# G4-Coral.net
KiCad netlist of a schematic drawn in Altium Designer
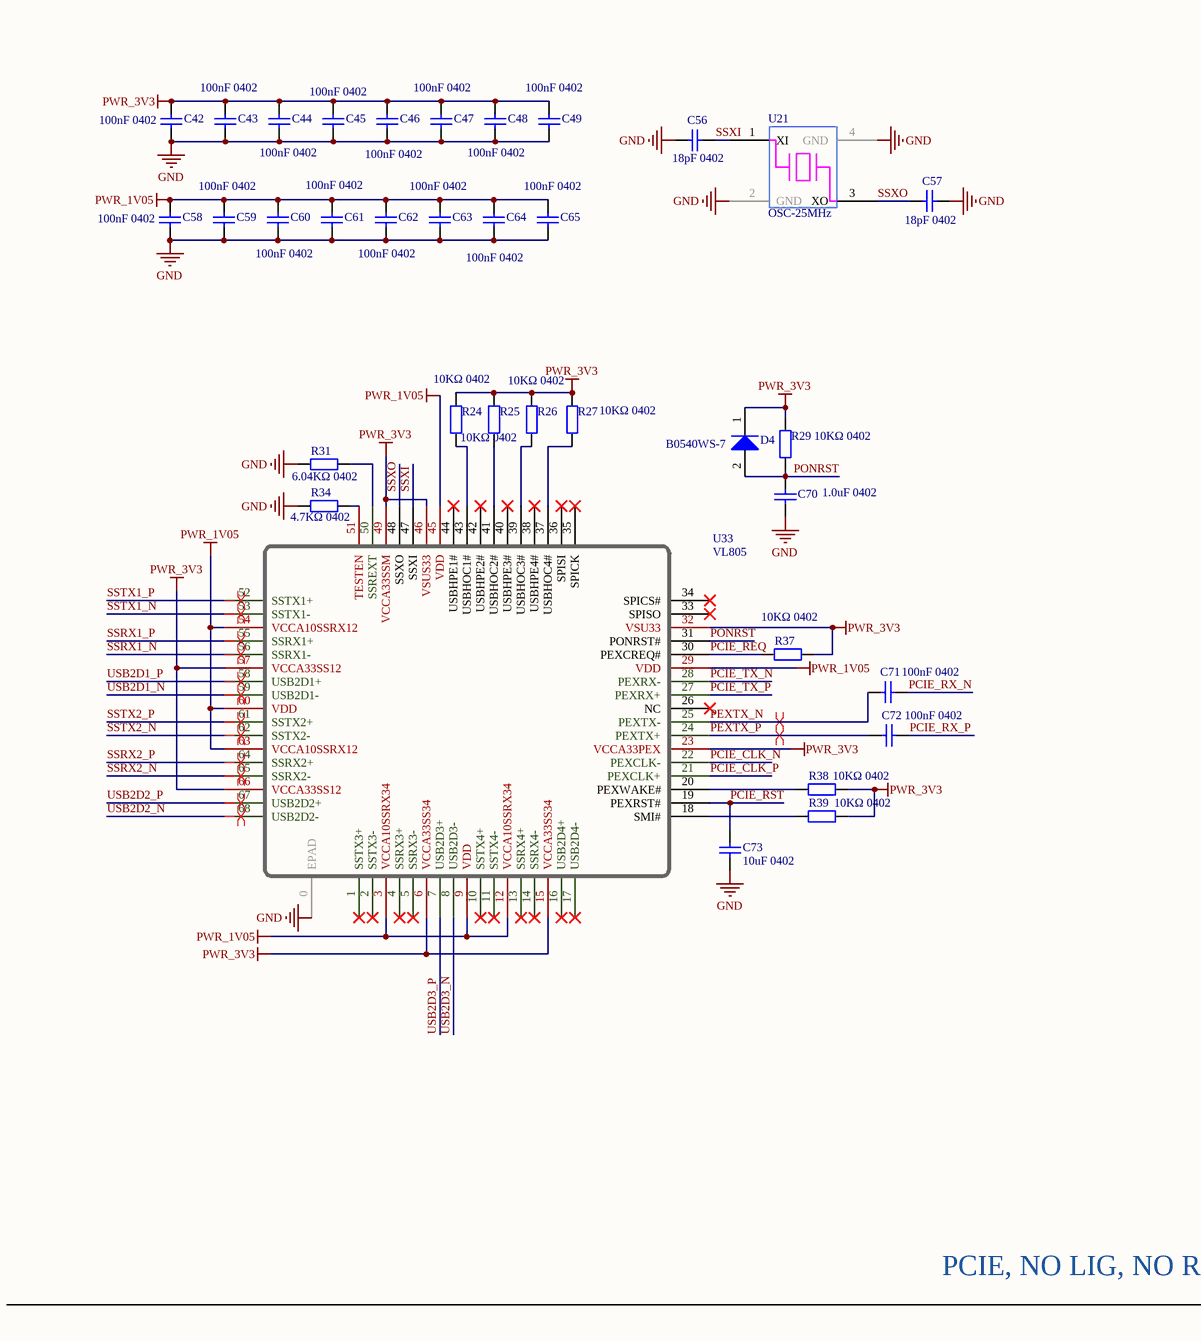
[diagram p0: G4-Coral.SchDoc, left]
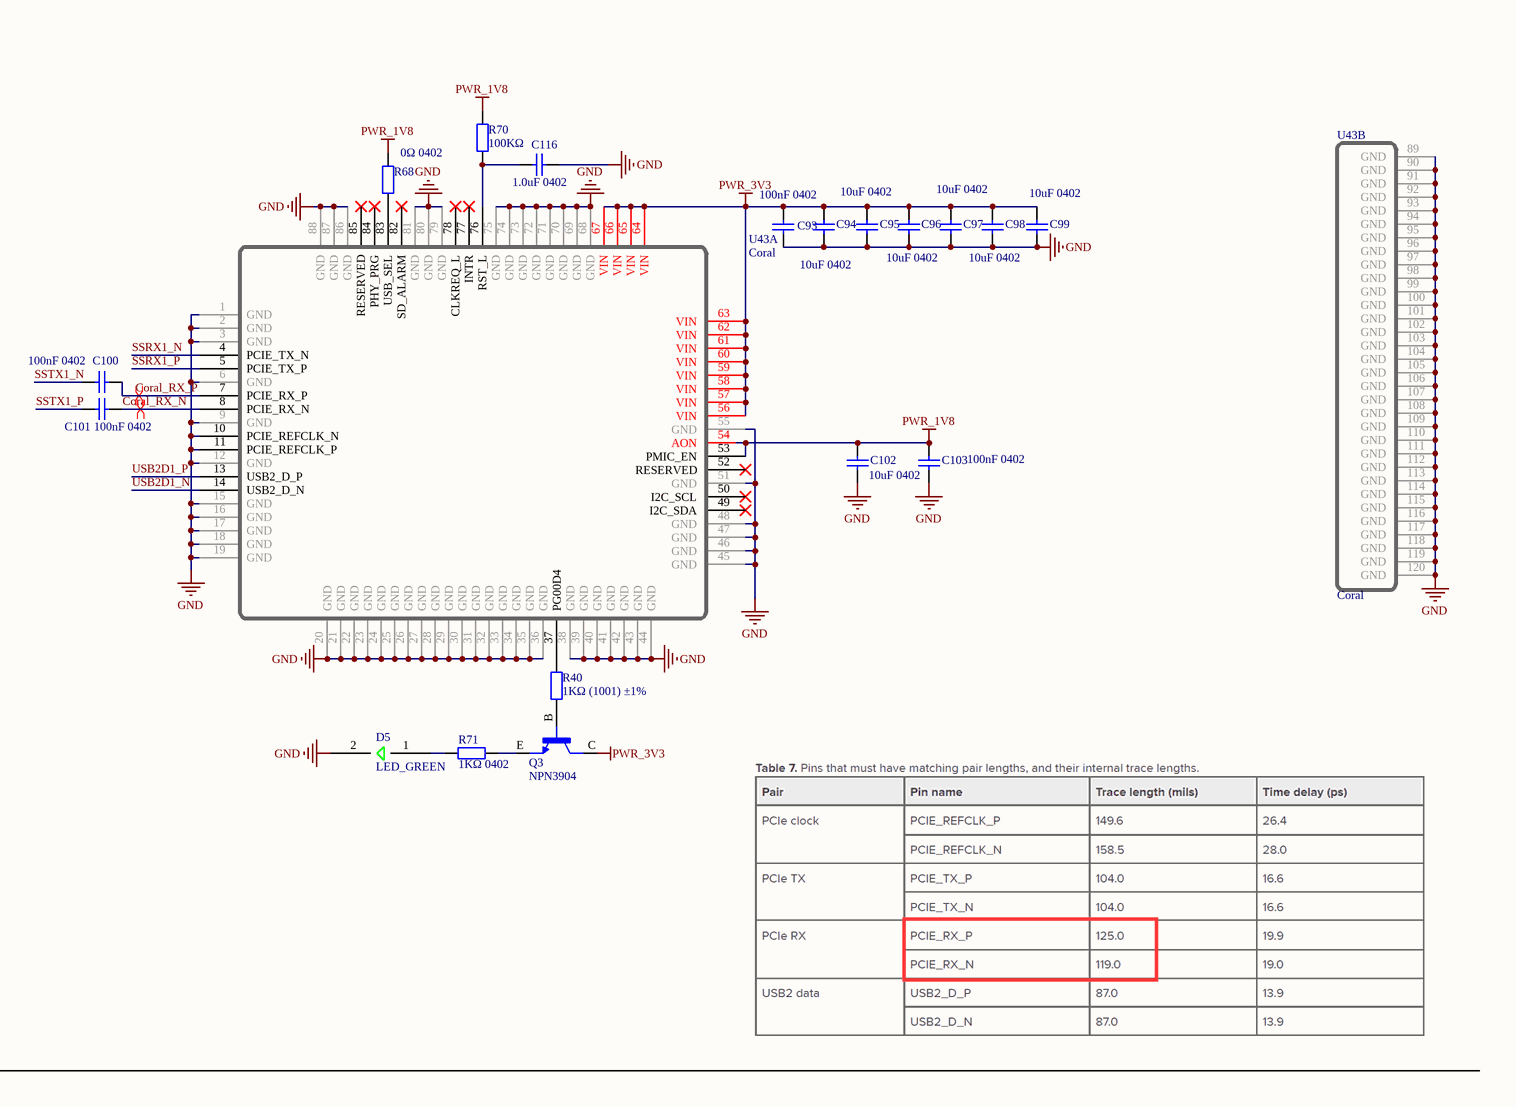
[diagram p1: G4-Coral.SchDoc, right]

(export (version "E")
  (design (tool "Eeschema 10.0.6"))
  (components
    (comp (ref "C42")
      (value "100nF 0402")
      (footprint "0402_C")
      (description "贴片电容")
      (libsource (lib "Miscellaneous Devices LC") (part "0402 100nF (104) 10% 16V"))
    )
    (comp (ref "C43")
      (value "100nF 0402")
      (footprint "0402_C")
      (description "贴片电容")
      (libsource (lib "Miscellaneous Devices LC") (part "0402 100nF (104) 10% 16V"))
    )
    (comp (ref "C44")
      (value "100nF 0402")
      (footprint "0402_C")
      (description "贴片电容")
      (libsource (lib "Miscellaneous Devices LC") (part "0402 100nF (104) 10% 16V"))
    )
    (comp (ref "C45")
      (value "100nF 0402")
      (footprint "0402_C")
      (description "贴片电容")
      (libsource (lib "Miscellaneous Devices LC") (part "0402 100nF (104) 10% 16V"))
    )
    (comp (ref "C46")
      (value "100nF 0402")
      (footprint "0402_C")
      (description "贴片电容")
      (libsource (lib "Miscellaneous Devices LC") (part "0402 100nF (104) 10% 16V"))
    )
    (comp (ref "C47")
      (value "100nF 0402")
      (footprint "0402_C")
      (description "贴片电容")
      (libsource (lib "Miscellaneous Devices LC") (part "0402 100nF (104) 10% 16V"))
    )
    (comp (ref "C48")
      (value "100nF 0402")
      (footprint "0402_C")
      (description "贴片电容")
      (libsource (lib "Miscellaneous Devices LC") (part "0402 100nF (104) 10% 16V"))
    )
    (comp (ref "C49")
      (value "100nF 0402")
      (footprint "0402_C")
      (description "贴片电容")
      (libsource (lib "Miscellaneous Devices LC") (part "0402 100nF (104) 10% 16V"))
    )
    (comp (ref "C56")
      (value "18pF 0402")
      (footprint "0402_C")
      (description "贴片电容")
      (libsource (lib "Miscellaneous Devices LC") (part "0402 18pF (180) 5% 50V"))
    )
    (comp (ref "C57")
      (value "18pF 0402")
      (footprint "0402_C")
      (description "贴片电容")
      (libsource (lib "Miscellaneous Devices LC") (part "0402 18pF (180) 5% 50V"))
    )
    (comp (ref "C58")
      (value "100nF 0402")
      (footprint "0402_C")
      (description "贴片电容")
      (libsource (lib "Miscellaneous Devices LC") (part "0402 100nF (104) 10% 16V"))
    )
    (comp (ref "C59")
      (value "100nF 0402")
      (footprint "0402_C")
      (description "贴片电容")
      (libsource (lib "Miscellaneous Devices LC") (part "0402 100nF (104) 10% 16V"))
    )
    (comp (ref "C60")
      (value "100nF 0402")
      (footprint "0402_C")
      (description "贴片电容")
      (libsource (lib "Miscellaneous Devices LC") (part "0402 100nF (104) 10% 16V"))
    )
    (comp (ref "C61")
      (value "100nF 0402")
      (footprint "0402_C")
      (description "贴片电容")
      (libsource (lib "Miscellaneous Devices LC") (part "0402 100nF (104) 10% 16V"))
    )
    (comp (ref "C62")
      (value "100nF 0402")
      (footprint "0402_C")
      (description "贴片电容")
      (libsource (lib "Miscellaneous Devices LC") (part "0402 100nF (104) 10% 16V"))
    )
    (comp (ref "C63")
      (value "100nF 0402")
      (footprint "0402_C")
      (description "贴片电容")
      (libsource (lib "Miscellaneous Devices LC") (part "0402 100nF (104) 10% 16V"))
    )
    (comp (ref "C64")
      (value "100nF 0402")
      (footprint "0402_C")
      (description "贴片电容")
      (libsource (lib "Miscellaneous Devices LC") (part "0402 100nF (104) 10% 16V"))
    )
    (comp (ref "C65")
      (value "100nF 0402")
      (footprint "0402_C")
      (description "贴片电容")
      (libsource (lib "Miscellaneous Devices LC") (part "0402 100nF (104) 10% 16V"))
    )
    (comp (ref "C70")
      (value "1.0uF 0402")
      (footprint "0402_C")
      (description "贴片电容")
      (libsource (lib "Miscellaneous Devices LC") (part "0402 1.0uF (105) 10% 25V"))
    )
    (comp (ref "C71")
      (value "100nF 0402")
      (footprint "0402_C")
      (description "贴片电容")
      (libsource (lib "Miscellaneous Devices LC") (part "0402 100nF (104) 10% 16V"))
    )
    (comp (ref "C72")
      (value "100nF 0402")
      (footprint "0402_C")
      (description "贴片电容")
      (libsource (lib "Miscellaneous Devices LC") (part "0402 100nF (104) 10% 16V"))
    )
    (comp (ref "C73")
      (value "10uF 0402")
      (footprint "0402_C")
      (description "贴片电容")
      (libsource (lib "Miscellaneous Devices LC") (part "0402 10uF (106) 20% 6.3V"))
    )
    (comp (ref "C93")
      (value "100nF 0402")
      (footprint "0402_C")
      (description "贴片电容")
      (libsource (lib "Miscellaneous Devices LC") (part "0402 100nF (104) 10% 16V"))
    )
    (comp (ref "C94")
      (value "10uF 0402")
      (footprint "0402_C")
      (description "贴片电容")
      (libsource (lib "Miscellaneous Devices LC") (part "0402 10uF (106) 20% 6.3V"))
    )
    (comp (ref "C95")
      (value "10uF 0402")
      (footprint "0402_C")
      (description "贴片电容")
      (libsource (lib "Miscellaneous Devices LC") (part "0402 10uF (106) 20% 6.3V"))
    )
    (comp (ref "C96")
      (value "10uF 0402")
      (footprint "0402_C")
      (description "贴片电容")
      (libsource (lib "Miscellaneous Devices LC") (part "0402 10uF (106) 20% 6.3V"))
    )
    (comp (ref "C97")
      (value "10uF 0402")
      (footprint "0402_C")
      (description "贴片电容")
      (libsource (lib "Miscellaneous Devices LC") (part "0402 10uF (106) 20% 6.3V"))
    )
    (comp (ref "C98")
      (value "10uF 0402")
      (footprint "0402_C")
      (description "贴片电容")
      (libsource (lib "Miscellaneous Devices LC") (part "0402 10uF (106) 20% 6.3V"))
    )
    (comp (ref "C99")
      (value "10uF 0402")
      (footprint "0402_C")
      (description "贴片电容")
      (libsource (lib "Miscellaneous Devices LC") (part "0402 10uF (106) 20% 6.3V"))
    )
    (comp (ref "C100")
      (value "100nF 0402")
      (footprint "0402_C")
      (description "贴片电容")
      (libsource (lib "Miscellaneous Devices LC") (part "0402 100nF (104) 10% 16V"))
    )
    (comp (ref "C101")
      (value "100nF 0402")
      (footprint "0402_C")
      (description "贴片电容")
      (libsource (lib "Miscellaneous Devices LC") (part "0402 100nF (104) 10% 16V"))
    )
    (comp (ref "C102")
      (value "10uF 0402")
      (footprint "0402_C")
      (description "贴片电容")
      (libsource (lib "Miscellaneous Devices LC") (part "0402 10uF (106) 20% 6.3V"))
    )
    (comp (ref "C103")
      (value "100nF 0402")
      (footprint "0402_C")
      (description "贴片电容")
      (libsource (lib "Miscellaneous Devices LC") (part "0402 100nF (104) 10% 16V"))
    )
    (comp (ref "C116")
      (value "1.0uF 0402")
      (footprint "0402_C")
      (description "贴片电容")
      (libsource (lib "Miscellaneous Devices LC") (part "0402 1.0uF (105) 10% 25V"))
    )
    (comp (ref "D4") (value "B0540WS-7") (footprint "B0540WS-7") (libsource (lib "Mars") (part "B0540WS-7")))
    (comp (ref "D5")
      (value "LED_GREEN")
      (footprint "LED_SIDE")
      (description "LED GREEN 0603 SIDE")
      (libsource (lib "bohao") (part "LED_GREEN"))
    )
    (comp (ref "Q3")
      (value "NPN3904")
      (footprint "NPN3904")
      (description "NPN 40V 200mA 300MHz 300mW Surface")
      (fields (field (name "MF") "ON Semiconductor") (field (name "MP") "MMBT3904LT1G"))
      (libsource (lib "bohao") (part "NPN3904"))
    )
    (comp (ref "R24")
      (value "10KΩ 0402")
      (footprint "0402_R")
      (description "贴片电阻")
      (libsource (lib "Miscellaneous Devices LC") (part "0402 10KΩ (1002) 1%"))
    )
    (comp (ref "R25")
      (value "10KΩ 0402")
      (footprint "0402_R")
      (description "贴片电阻")
      (libsource (lib "Miscellaneous Devices LC") (part "0402 10KΩ (1002) 1%"))
    )
    (comp (ref "R26")
      (value "10KΩ 0402")
      (footprint "0402_R")
      (description "贴片电阻")
      (libsource (lib "Miscellaneous Devices LC") (part "0402 10KΩ (1002) 1%"))
    )
    (comp (ref "R27")
      (value "10KΩ 0402")
      (footprint "0402_R")
      (description "贴片电阻")
      (libsource (lib "Miscellaneous Devices LC") (part "0402 10KΩ (1002) 1%"))
    )
    (comp (ref "R29")
      (value "10KΩ 0402")
      (footprint "0402_R")
      (description "贴片电阻")
      (libsource (lib "Miscellaneous Devices LC") (part "0402 10KΩ (1002) 1%"))
    )
    (comp (ref "R31")
      (value "6.04KΩ 0402")
      (footprint "0402_R")
      (description "贴片电阻")
      (libsource (lib "Miscellaneous Devices LC") (part "0402 5.6KΩ (5601) 1%"))
    )
    (comp (ref "R34")
      (value "4.7KΩ 0402")
      (footprint "0402_R")
      (description "贴片电阻")
      (libsource (lib "Miscellaneous Devices LC") (part "0402 4.7KΩ (4701) 1%"))
    )
    (comp (ref "R37")
      (value "10KΩ 0402")
      (footprint "0402_R")
      (description "贴片电阻")
      (libsource (lib "") (part "0402 10KΩ (1002) 1%_1"))
    )
    (comp (ref "R38")
      (value "10KΩ 0402")
      (footprint "0402_R")
      (description "贴片电阻")
      (libsource (lib "") (part "0402 10KΩ (1002) 1%_1"))
    )
    (comp (ref "R39")
      (value "10KΩ 0402")
      (footprint "0402_R")
      (description "贴片电阻")
      (libsource (lib "") (part "0402 10KΩ (1002) 1%_1"))
    )
    (comp (ref "R40")
      (value "1KΩ (1001) ±1%")
      (footprint "0402_R")
      (description "贴片电阻")
      (libsource (lib "") (part "0402 1KΩ (1001) 1%_1"))
    )
    (comp (ref "R68")
      (value "0Ω 0402")
      (footprint "0402_R")
      (description "贴片电阻")
      (libsource (lib "Miscellaneous Devices LC") (part "0402 0Ω (0R0) 1%"))
    )
    (comp (ref "R70")
      (value "100KΩ")
      (footprint "0402_R")
      (description "贴片电阻")
      (libsource (lib "Miscellaneous Devices LC") (part "0402 100KΩ (1003) 1%"))
    )
    (comp (ref "R71")
      (value "1KΩ 0402")
      (footprint "0402_R")
      (description "贴片电阻")
      (libsource (lib "Miscellaneous Devices LC") (part "0402 1KΩ (1001) 1%"))
    )
    (comp (ref "U21")
      (value "OSC-25MHz")
      (footprint "OSC-25MHz")
      (description "Passive crystal oscillator")
      (libsource (lib "Mars") (part "OSC-25MHz"))
    )
    (comp (ref "U33")
      (value "VL805")
      (footprint "VL805")
      (description "PCIe to USB3.0")
      (libsource (lib "bohao") (part "VL805"))
    )
    (comp (ref "U43")
      (value "Coral")
      (footprint "Coral")
      (description "G313-06329-00")
      (libsource (lib "bohao") (part "Coral"))
    )
  )
  (nets
    (net (code "1") (name "/Coral_RX_N") (class "Default")
      (node (ref "C101") (pin "2") (pinfunction "2_2") (pintype "passive"))
      (node (ref "U43") (pin "8") (pinfunction "PCIE_RX_N_8") (pintype "passive"))
    )
    (net (code "2") (name "/Coral_RX_P") (class "Default")
      (node (ref "C100") (pin "2") (pinfunction "2_2") (pintype "passive"))
      (node (ref "U43") (pin "7") (pinfunction "PCIE_RX_P_7") (pintype "passive"))
    )
    (net (code "3") (name "/PCIE_CLK_N") (class "Default")
      (node (ref "U33") (pin "22") (pinfunction "PEXCLK-_22") (pintype "passive"))
    )
    (net (code "4") (name "/PCIE_CLK_P") (class "Default")
      (node (ref "U33") (pin "21") (pinfunction "PEXCLK+_21") (pintype "passive"))
    )
    (net (code "5") (name "/PCIE_REQ") (class "Default")
      (node (ref "R37") (pin "1") (pinfunction "1_1") (pintype "passive"))
      (node (ref "U33") (pin "30") (pinfunction "PEXCREQ#_30") (pintype "passive"))
    )
    (net (code "6") (name "/PCIE_RST") (class "Default")
      (node (ref "C73") (pin "2") (pinfunction "2_2") (pintype "passive"))
      (node (ref "U33") (pin "19") (pinfunction "PEXRST#_19") (pintype "passive"))
    )
    (net (code "7") (name "/PCIE_RX_N") (class "Default")
      (node (ref "C71") (pin "2") (pinfunction "2_2") (pintype "passive"))
    )
    (net (code "8") (name "/PCIE_RX_P") (class "Default")
      (node (ref "C72") (pin "2") (pinfunction "2_2") (pintype "passive"))
    )
    (net (code "9") (name "/PCIE_TX_N") (class "Default")
      (node (ref "U33") (pin "28") (pinfunction "PEXRX-_28") (pintype "passive"))
    )
    (net (code "10") (name "/PCIE_TX_P") (class "Default")
      (node (ref "U33") (pin "27") (pinfunction "PEXRX+_27") (pintype "passive"))
    )
    (net (code "11") (name "/PEXTX_N") (class "Default")
      (node (ref "C71") (pin "1") (pinfunction "1_1") (pintype "passive"))
      (node (ref "U33") (pin "25") (pinfunction "PEXTX-_25") (pintype "passive"))
    )
    (net (code "12") (name "/PEXTX_P") (class "Default")
      (node (ref "C72") (pin "1") (pinfunction "1_1") (pintype "passive"))
      (node (ref "U33") (pin "24") (pinfunction "PEXTX+_24") (pintype "passive"))
    )
    (net (code "13") (name "/PONRST") (class "Default")
      (node (ref "C70") (pin "1") (pinfunction "1_1") (pintype "passive"))
      (node (ref "D4") (pin "2") (pinfunction "A_2") (pintype "passive"))
      (node (ref "R29") (pin "1") (pinfunction "1_1") (pintype "passive"))
      (node (ref "U33") (pin "31") (pinfunction "PONRST#_31") (pintype "passive"))
    )
    (net (code "14") (name "/SSRX1_N") (class "Default")
      (node (ref "U33") (pin "56") (pinfunction "SSRX1-_56") (pintype "passive"))
      (node (ref "U43") (pin "4") (pinfunction "PCIE_TX_N_4") (pintype "passive"))
    )
    (net (code "15") (name "/SSRX1_P") (class "Default")
      (node (ref "U33") (pin "55") (pinfunction "SSRX1+_55") (pintype "passive"))
      (node (ref "U43") (pin "5") (pinfunction "PCIE_TX_P_5") (pintype "passive"))
    )
    (net (code "16") (name "/SSRX2_N") (class "Default")
      (node (ref "U33") (pin "65") (pinfunction "SSRX2-_65") (pintype "passive"))
    )
    (net (code "17") (name "/SSRX2_P") (class "Default")
      (node (ref "U33") (pin "64") (pinfunction "SSRX2+_64") (pintype "passive"))
    )
    (net (code "18") (name "/SSTX1_N") (class "Default")
      (node (ref "C100") (pin "1") (pinfunction "1_1") (pintype "passive"))
      (node (ref "U33") (pin "53") (pinfunction "SSTX1-_53") (pintype "passive"))
    )
    (net (code "19") (name "/SSTX1_P") (class "Default")
      (node (ref "C101") (pin "1") (pinfunction "1_1") (pintype "passive"))
      (node (ref "U33") (pin "52") (pinfunction "SSTX1+_52") (pintype "passive"))
    )
    (net (code "20") (name "/SSTX2_N") (class "Default")
      (node (ref "U33") (pin "62") (pinfunction "SSTX2-_62") (pintype "passive"))
    )
    (net (code "21") (name "/SSTX2_P") (class "Default")
      (node (ref "U33") (pin "61") (pinfunction "SSTX2+_61") (pintype "passive"))
    )
    (net (code "22") (name "/SSXI") (class "Default")
      (node (ref "C56") (pin "2") (pinfunction "2_2") (pintype "passive"))
      (node (ref "U21") (pin "1") (pinfunction "XI_1") (pintype "passive"))
      (node (ref "U33") (pin "47") (pinfunction "SSXI_47") (pintype "passive"))
    )
    (net (code "23") (name "/SSXO") (class "Default")
      (node (ref "C57") (pin "1") (pinfunction "1_1") (pintype "passive"))
      (node (ref "U21") (pin "3") (pinfunction "XO_3") (pintype "passive"))
      (node (ref "U33") (pin "48") (pinfunction "SSXO_48") (pintype "passive"))
    )
    (net (code "24") (name "/USB2D1_N") (class "Default")
      (node (ref "U33") (pin "59") (pinfunction "USB2D1-_59") (pintype "passive"))
      (node (ref "U43") (pin "14") (pinfunction "USB2_D_N_14") (pintype "passive"))
    )
    (net (code "25") (name "/USB2D1_P") (class "Default")
      (node (ref "U33") (pin "58") (pinfunction "USB2D1+_58") (pintype "passive"))
      (node (ref "U43") (pin "13") (pinfunction "USB2_D_P_13") (pintype "passive"))
    )
    (net (code "26") (name "/USB2D2_N") (class "Default")
      (node (ref "U33") (pin "68") (pinfunction "USB2D2-_68") (pintype "passive"))
    )
    (net (code "27") (name "/USB2D2_P") (class "Default")
      (node (ref "U33") (pin "67") (pinfunction "USB2D2+_67") (pintype "passive"))
    )
    (net (code "28") (name "/USB2D3_N") (class "Default")
      (node (ref "U33") (pin "8") (pinfunction "USB2D3-_8") (pintype "passive"))
    )
    (net (code "29") (name "/USB2D3_P") (class "Default")
      (node (ref "U33") (pin "7") (pinfunction "USB2D3+_7") (pintype "passive"))
    )
    (net (code "30") (name "GND") (class "Default")
      (node (ref "C102") (pin "1") (pinfunction "1_1") (pintype "passive"))
      (node (ref "C103") (pin "1") (pinfunction "1_1") (pintype "passive"))
      (node (ref "C116") (pin "1") (pinfunction "1_1") (pintype "passive"))
      (node (ref "C42") (pin "1") (pinfunction "1_1") (pintype "passive"))
      (node (ref "C43") (pin "1") (pinfunction "1_1") (pintype "passive"))
      (node (ref "C44") (pin "1") (pinfunction "1_1") (pintype "passive"))
      (node (ref "C45") (pin "1") (pinfunction "1_1") (pintype "passive"))
      (node (ref "C46") (pin "1") (pinfunction "1_1") (pintype "passive"))
      (node (ref "C47") (pin "1") (pinfunction "1_1") (pintype "passive"))
      (node (ref "C48") (pin "1") (pinfunction "1_1") (pintype "passive"))
      (node (ref "C49") (pin "1") (pinfunction "1_1") (pintype "passive"))
      (node (ref "C56") (pin "1") (pinfunction "1_1") (pintype "passive"))
      (node (ref "C57") (pin "2") (pinfunction "2_2") (pintype "passive"))
      (node (ref "C58") (pin "1") (pinfunction "1_1") (pintype "passive"))
      (node (ref "C59") (pin "1") (pinfunction "1_1") (pintype "passive"))
      (node (ref "C60") (pin "1") (pinfunction "1_1") (pintype "passive"))
      (node (ref "C61") (pin "1") (pinfunction "1_1") (pintype "passive"))
      (node (ref "C62") (pin "1") (pinfunction "1_1") (pintype "passive"))
      (node (ref "C63") (pin "1") (pinfunction "1_1") (pintype "passive"))
      (node (ref "C64") (pin "1") (pinfunction "1_1") (pintype "passive"))
      (node (ref "C65") (pin "1") (pinfunction "1_1") (pintype "passive"))
      (node (ref "C70") (pin "2") (pinfunction "2_2") (pintype "passive"))
      (node (ref "C73") (pin "1") (pinfunction "1_1") (pintype "passive"))
      (node (ref "C93") (pin "1") (pinfunction "1_1") (pintype "passive"))
      (node (ref "C94") (pin "1") (pinfunction "1_1") (pintype "passive"))
      (node (ref "C95") (pin "1") (pinfunction "1_1") (pintype "passive"))
      (node (ref "C96") (pin "1") (pinfunction "1_1") (pintype "passive"))
      (node (ref "C97") (pin "1") (pinfunction "1_1") (pintype "passive"))
      (node (ref "C98") (pin "1") (pinfunction "1_1") (pintype "passive"))
      (node (ref "C99") (pin "1") (pinfunction "1_1") (pintype "passive"))
      (node (ref "D5") (pin "2") (pintype "passive"))
      (node (ref "R31") (pin "2") (pinfunction "2_2") (pintype "passive"))
      (node (ref "R34") (pin "2") (pinfunction "2_2") (pintype "passive"))
      (node (ref "U21") (pin "2") (pinfunction "GND_2") (pintype "passive"))
      (node (ref "U21") (pin "4") (pinfunction "GND_4") (pintype "passive"))
      (node (ref "U33") (pin "0") (pinfunction "EPAD_0") (pintype "passive"))
      (node (ref "U43") (pin "1") (pinfunction "GND_1") (pintype "power_in"))
      (node (ref "U43") (pin "10") (pinfunction "PCIE_REFCLK_N_10") (pintype "passive"))
      (node (ref "U43") (pin "100") (pinfunction "GND_100") (pintype "power_in"))
      (node (ref "U43") (pin "101") (pinfunction "GND_101") (pintype "power_in"))
      (node (ref "U43") (pin "102") (pinfunction "GND_102") (pintype "power_in"))
      (node (ref "U43") (pin "103") (pinfunction "GND_103") (pintype "power_in"))
      (node (ref "U43") (pin "104") (pinfunction "GND_104") (pintype "power_in"))
      (node (ref "U43") (pin "105") (pinfunction "GND_105") (pintype "power_in"))
      (node (ref "U43") (pin "106") (pinfunction "GND_106") (pintype "power_in"))
      (node (ref "U43") (pin "107") (pinfunction "GND_107") (pintype "power_in"))
      (node (ref "U43") (pin "108") (pinfunction "GND_108") (pintype "power_in"))
      (node (ref "U43") (pin "109") (pinfunction "GND_109") (pintype "power_in"))
      (node (ref "U43") (pin "11") (pinfunction "PCIE_REFCLK_P_11") (pintype "passive"))
      (node (ref "U43") (pin "110") (pinfunction "GND_110") (pintype "power_in"))
      (node (ref "U43") (pin "111") (pinfunction "GND_111") (pintype "power_in"))
      (node (ref "U43") (pin "112") (pinfunction "GND_112") (pintype "power_in"))
      (node (ref "U43") (pin "113") (pinfunction "GND_113") (pintype "power_in"))
      (node (ref "U43") (pin "114") (pinfunction "GND_114") (pintype "power_in"))
      (node (ref "U43") (pin "115") (pinfunction "GND_115") (pintype "power_in"))
      (node (ref "U43") (pin "116") (pinfunction "GND_116") (pintype "power_in"))
      (node (ref "U43") (pin "117") (pinfunction "GND_117") (pintype "power_in"))
      (node (ref "U43") (pin "118") (pinfunction "GND_118") (pintype "power_in"))
      (node (ref "U43") (pin "119") (pinfunction "GND_119") (pintype "power_in"))
      (node (ref "U43") (pin "12") (pinfunction "GND_12") (pintype "passive"))
      (node (ref "U43") (pin "120") (pinfunction "GND_120") (pintype "power_in"))
      (node (ref "U43") (pin "15") (pinfunction "GND_15") (pintype "passive"))
      (node (ref "U43") (pin "16") (pinfunction "GND_16") (pintype "passive"))
      (node (ref "U43") (pin "17") (pinfunction "GND_17") (pintype "passive"))
      (node (ref "U43") (pin "18") (pinfunction "GND_18") (pintype "passive"))
      (node (ref "U43") (pin "19") (pinfunction "GND_19") (pintype "passive"))
      (node (ref "U43") (pin "2") (pinfunction "GND_2") (pintype "passive"))
      (node (ref "U43") (pin "20") (pinfunction "GND_20") (pintype "power_in"))
      (node (ref "U43") (pin "21") (pinfunction "GND_21") (pintype "power_in"))
      (node (ref "U43") (pin "22") (pinfunction "GND_22") (pintype "power_in"))
      (node (ref "U43") (pin "23") (pinfunction "GND_23") (pintype "power_in"))
      (node (ref "U43") (pin "24") (pinfunction "GND_24") (pintype "power_in"))
      (node (ref "U43") (pin "25") (pinfunction "GND_25") (pintype "power_in"))
      (node (ref "U43") (pin "26") (pinfunction "GND_26") (pintype "power_in"))
      (node (ref "U43") (pin "27") (pinfunction "GND_27") (pintype "power_in"))
      (node (ref "U43") (pin "28") (pinfunction "GND_28") (pintype "power_in"))
      (node (ref "U43") (pin "29") (pinfunction "GND_29") (pintype "power_in"))
      (node (ref "U43") (pin "3") (pinfunction "GND_3") (pintype "passive"))
      (node (ref "U43") (pin "30") (pinfunction "GND_30") (pintype "power_in"))
      (node (ref "U43") (pin "31") (pinfunction "GND_31") (pintype "power_in"))
      (node (ref "U43") (pin "32") (pinfunction "GND_32") (pintype "power_in"))
      (node (ref "U43") (pin "33") (pinfunction "GND_33") (pintype "power_in"))
      (node (ref "U43") (pin "34") (pinfunction "GND_34") (pintype "power_in"))
      (node (ref "U43") (pin "35") (pinfunction "GND_35") (pintype "power_in"))
      (node (ref "U43") (pin "36") (pinfunction "GND_36") (pintype "power_in"))
      (node (ref "U43") (pin "38") (pinfunction "GND_38") (pintype "power_in"))
      (node (ref "U43") (pin "39") (pinfunction "GND_39") (pintype "power_in"))
      (node (ref "U43") (pin "40") (pinfunction "GND_40") (pintype "power_in"))
      (node (ref "U43") (pin "41") (pinfunction "GND_41") (pintype "power_in"))
      (node (ref "U43") (pin "42") (pinfunction "GND_42") (pintype "power_in"))
      (node (ref "U43") (pin "43") (pinfunction "GND_43") (pintype "power_in"))
      (node (ref "U43") (pin "44") (pinfunction "GND_44") (pintype "power_in"))
      (node (ref "U43") (pin "45") (pinfunction "GND_45") (pintype "power_in"))
      (node (ref "U43") (pin "46") (pinfunction "GND_46") (pintype "passive"))
      (node (ref "U43") (pin "47") (pinfunction "GND_47") (pintype "passive"))
      (node (ref "U43") (pin "48") (pinfunction "GND_48") (pintype "passive"))
      (node (ref "U43") (pin "51") (pinfunction "GND_51") (pintype "passive"))
      (node (ref "U43") (pin "55") (pinfunction "GND_55") (pintype "passive"))
      (node (ref "U43") (pin "6") (pinfunction "GND_6") (pintype "passive"))
      (node (ref "U43") (pin "68") (pinfunction "GND_68") (pintype "power_in"))
      (node (ref "U43") (pin "69") (pinfunction "GND_69") (pintype "power_in"))
      (node (ref "U43") (pin "70") (pinfunction "GND_70") (pintype "power_in"))
      (node (ref "U43") (pin "71") (pinfunction "GND_71") (pintype "power_in"))
      (node (ref "U43") (pin "72") (pinfunction "GND_72") (pintype "power_in"))
      (node (ref "U43") (pin "73") (pinfunction "GND_73") (pintype "power_in"))
      (node (ref "U43") (pin "74") (pinfunction "GND_74") (pintype "power_in"))
      (node (ref "U43") (pin "75") (pinfunction "GND_75") (pintype "power_in"))
      (node (ref "U43") (pin "79") (pinfunction "GND_79") (pintype "power_in"))
      (node (ref "U43") (pin "80") (pinfunction "GND_80") (pintype "power_in"))
      (node (ref "U43") (pin "81") (pinfunction "GND_81") (pintype "power_in"))
      (node (ref "U43") (pin "86") (pinfunction "GND_86") (pintype "power_in"))
      (node (ref "U43") (pin "87") (pinfunction "GND_87") (pintype "power_in"))
      (node (ref "U43") (pin "88") (pinfunction "GND_88") (pintype "power_in"))
      (node (ref "U43") (pin "89") (pinfunction "GND_89") (pintype "power_in"))
      (node (ref "U43") (pin "9") (pinfunction "GND_9") (pintype "passive"))
      (node (ref "U43") (pin "90") (pinfunction "GND_90") (pintype "power_in"))
      (node (ref "U43") (pin "91") (pinfunction "GND_91") (pintype "power_in"))
      (node (ref "U43") (pin "92") (pinfunction "GND_92") (pintype "power_in"))
      (node (ref "U43") (pin "93") (pinfunction "GND_93") (pintype "power_in"))
      (node (ref "U43") (pin "94") (pinfunction "GND_94") (pintype "power_in"))
      (node (ref "U43") (pin "95") (pinfunction "GND_95") (pintype "power_in"))
      (node (ref "U43") (pin "96") (pinfunction "GND_96") (pintype "power_in"))
      (node (ref "U43") (pin "97") (pinfunction "GND_97") (pintype "power_in"))
      (node (ref "U43") (pin "98") (pinfunction "GND_98") (pintype "power_in"))
      (node (ref "U43") (pin "99") (pinfunction "GND_99") (pintype "power_in"))
    )
    (net (code "31") (name "Net-(D5-Pad1)") (class "Default")
      (node (ref "D5") (pin "1") (pintype "passive"))
      (node (ref "R71") (pin "1") (pinfunction "1_1") (pintype "passive"))
    )
    (net (code "32") (name "Net-(Q3-PadB)") (class "Default")
      (node (ref "Q3") (pin "B") (pinfunction "B_B") (pintype "passive"))
      (node (ref "R40") (pin "1") (pinfunction "1_1") (pintype "passive"))
    )
    (net (code "33") (name "Net-(Q3-PadE)") (class "Default")
      (node (ref "Q3") (pin "E") (pinfunction "E_E") (pintype "passive"))
      (node (ref "R71") (pin "2") (pinfunction "2_2") (pintype "passive"))
    )
    (net (code "34") (name "Net-(U33-PEXWAKE#)") (class "Default")
      (node (ref "R38") (pin "1") (pinfunction "1_1") (pintype "passive"))
      (node (ref "U33") (pin "20") (pinfunction "PEXWAKE#_20") (pintype "passive"))
    )
    (net (code "35") (name "Net-(U33-SMI#)") (class "Default")
      (node (ref "R39") (pin "1") (pinfunction "1_1") (pintype "passive"))
      (node (ref "U33") (pin "18") (pinfunction "SMI#_18") (pintype "passive"))
    )
    (net (code "36") (name "Net-(U33-SSREXT)") (class "Default")
      (node (ref "R31") (pin "1") (pinfunction "1_1") (pintype "passive"))
      (node (ref "U33") (pin "50") (pinfunction "SSREXT_50") (pintype "passive"))
    )
    (net (code "37") (name "Net-(U33-TESTEN)") (class "Default")
      (node (ref "R34") (pin "1") (pinfunction "1_1") (pintype "passive"))
      (node (ref "U33") (pin "51") (pinfunction "TESTEN_51") (pintype "passive"))
    )
    (net (code "38") (name "Net-(U33-USBHOC1#)") (class "Default")
      (node (ref "R24") (pin "1") (pinfunction "1_1") (pintype "passive"))
      (node (ref "U33") (pin "43") (pinfunction "USBHOC1#_43") (pintype "passive"))
    )
    (net (code "39") (name "Net-(U33-USBHOC2#)") (class "Default")
      (node (ref "R25") (pin "1") (pinfunction "1_1") (pintype "passive"))
      (node (ref "U33") (pin "41") (pinfunction "USBHOC2#_41") (pintype "passive"))
    )
    (net (code "40") (name "Net-(U33-USBHOC3#)") (class "Default")
      (node (ref "R26") (pin "1") (pinfunction "1_1") (pintype "passive"))
      (node (ref "U33") (pin "39") (pinfunction "USBHOC3#_39") (pintype "passive"))
    )
    (net (code "41") (name "Net-(U33-USBHOC4#)") (class "Default")
      (node (ref "R27") (pin "1") (pinfunction "1_1") (pintype "passive"))
      (node (ref "U33") (pin "37") (pinfunction "USBHOC4#_37") (pintype "passive"))
    )
    (net (code "42") (name "Net-(U43A-PG00D4)") (class "Default")
      (node (ref "R40") (pin "2") (pinfunction "2_2") (pintype "passive"))
      (node (ref "U43") (pin "37") (pinfunction "PG00D4_37") (pintype "power_in"))
    )
    (net (code "43") (name "Net-(U43A-RST_L)") (class "Default")
      (node (ref "C116") (pin "2") (pinfunction "2_2") (pintype "passive"))
      (node (ref "R70") (pin "1") (pinfunction "1_1") (pintype "passive"))
      (node (ref "U43") (pin "76") (pinfunction "RST_L_76") (pintype "power_in"))
    )
    (net (code "44") (name "Net-(U43A-USB_SEL)") (class "Default")
      (node (ref "R68") (pin "1") (pinfunction "1_1") (pintype "passive"))
      (node (ref "U43") (pin "83") (pinfunction "USB_SEL_83") (pintype "power_in"))
    )
    (net (code "45") (name "PWR_1V05") (class "Default")
      (node (ref "C58") (pin "2") (pinfunction "2_2") (pintype "passive"))
      (node (ref "C59") (pin "2") (pinfunction "2_2") (pintype "passive"))
      (node (ref "C60") (pin "2") (pinfunction "2_2") (pintype "passive"))
      (node (ref "C61") (pin "2") (pinfunction "2_2") (pintype "passive"))
      (node (ref "C62") (pin "2") (pinfunction "2_2") (pintype "passive"))
      (node (ref "C63") (pin "2") (pinfunction "2_2") (pintype "passive"))
      (node (ref "C64") (pin "2") (pinfunction "2_2") (pintype "passive"))
      (node (ref "C65") (pin "2") (pinfunction "2_2") (pintype "passive"))
      (node (ref "U33") (pin "12") (pinfunction "VCCA10SSRX34_12") (pintype "passive"))
      (node (ref "U33") (pin "29") (pinfunction "VDD_29") (pintype "passive"))
      (node (ref "U33") (pin "3") (pinfunction "VCCA10SSRX34_3") (pintype "passive"))
      (node (ref "U33") (pin "45") (pinfunction "VDD_45") (pintype "passive"))
      (node (ref "U33") (pin "54") (pinfunction "VCCA10SSRX12_54") (pintype "passive"))
      (node (ref "U33") (pin "60") (pinfunction "VDD_60") (pintype "passive"))
      (node (ref "U33") (pin "63") (pinfunction "VCCA10SSRX12_63") (pintype "passive"))
      (node (ref "U33") (pin "9") (pinfunction "VDD_9") (pintype "passive"))
    )
    (net (code "46") (name "PWR_1V8") (class "Default")
      (node (ref "C102") (pin "2") (pinfunction "2_2") (pintype "passive"))
      (node (ref "C103") (pin "2") (pinfunction "2_2") (pintype "passive"))
      (node (ref "R68") (pin "2") (pinfunction "2_2") (pintype "passive"))
      (node (ref "R70") (pin "2") (pinfunction "2_2") (pintype "passive"))
      (node (ref "U43") (pin "53") (pinfunction "PMIC_EN_53") (pintype "passive"))
      (node (ref "U43") (pin "54") (pinfunction "AON_54") (pintype "passive"))
    )
    (net (code "47") (name "PWR_3V3") (class "Default")
      (node (ref "C42") (pin "2") (pinfunction "2_2") (pintype "passive"))
      (node (ref "C43") (pin "2") (pinfunction "2_2") (pintype "passive"))
      (node (ref "C44") (pin "2") (pinfunction "2_2") (pintype "passive"))
      (node (ref "C45") (pin "2") (pinfunction "2_2") (pintype "passive"))
      (node (ref "C46") (pin "2") (pinfunction "2_2") (pintype "passive"))
      (node (ref "C47") (pin "2") (pinfunction "2_2") (pintype "passive"))
      (node (ref "C48") (pin "2") (pinfunction "2_2") (pintype "passive"))
      (node (ref "C49") (pin "2") (pinfunction "2_2") (pintype "passive"))
      (node (ref "C93") (pin "2") (pinfunction "2_2") (pintype "passive"))
      (node (ref "C94") (pin "2") (pinfunction "2_2") (pintype "passive"))
      (node (ref "C95") (pin "2") (pinfunction "2_2") (pintype "passive"))
      (node (ref "C96") (pin "2") (pinfunction "2_2") (pintype "passive"))
      (node (ref "C97") (pin "2") (pinfunction "2_2") (pintype "passive"))
      (node (ref "C98") (pin "2") (pinfunction "2_2") (pintype "passive"))
      (node (ref "C99") (pin "2") (pinfunction "2_2") (pintype "passive"))
      (node (ref "D4") (pin "1") (pinfunction "K_1") (pintype "passive"))
      (node (ref "Q3") (pin "C") (pinfunction "C_C") (pintype "passive"))
      (node (ref "R24") (pin "2") (pinfunction "2_2") (pintype "passive"))
      (node (ref "R25") (pin "2") (pinfunction "2_2") (pintype "passive"))
      (node (ref "R26") (pin "2") (pinfunction "2_2") (pintype "passive"))
      (node (ref "R27") (pin "2") (pinfunction "2_2") (pintype "passive"))
      (node (ref "R29") (pin "2") (pinfunction "2_2") (pintype "passive"))
      (node (ref "R37") (pin "2") (pinfunction "2_2") (pintype "passive"))
      (node (ref "R38") (pin "2") (pinfunction "2_2") (pintype "passive"))
      (node (ref "R39") (pin "2") (pinfunction "2_2") (pintype "passive"))
      (node (ref "U33") (pin "15") (pinfunction "VCCA33SS34_15") (pintype "passive"))
      (node (ref "U33") (pin "23") (pinfunction "VCCA33PEX_23") (pintype "passive"))
      (node (ref "U33") (pin "32") (pinfunction "VSU33_32") (pintype "passive"))
      (node (ref "U33") (pin "46") (pinfunction "VSUS33_46") (pintype "passive"))
      (node (ref "U33") (pin "49") (pinfunction "VCCA33SSM_49") (pintype "passive"))
      (node (ref "U33") (pin "57") (pinfunction "VCCA33SS12_57") (pintype "passive"))
      (node (ref "U33") (pin "6") (pinfunction "VCCA33SS34_6") (pintype "passive"))
      (node (ref "U33") (pin "66") (pinfunction "VCCA33SS12_66") (pintype "passive"))
      (node (ref "U43") (pin "56") (pinfunction "VIN_56") (pintype "passive"))
      (node (ref "U43") (pin "57") (pinfunction "VIN_57") (pintype "passive"))
      (node (ref "U43") (pin "58") (pinfunction "VIN_58") (pintype "passive"))
      (node (ref "U43") (pin "59") (pinfunction "VIN_59") (pintype "passive"))
      (node (ref "U43") (pin "60") (pinfunction "VIN_60") (pintype "passive"))
      (node (ref "U43") (pin "61") (pinfunction "VIN_61") (pintype "passive"))
      (node (ref "U43") (pin "62") (pinfunction "VIN_62") (pintype "passive"))
      (node (ref "U43") (pin "63") (pinfunction "VIN_63") (pintype "passive"))
      (node (ref "U43") (pin "64") (pinfunction "VIN_64") (pintype "power_in"))
      (node (ref "U43") (pin "65") (pinfunction "VIN_65") (pintype "power_in"))
      (node (ref "U43") (pin "66") (pinfunction "VIN_66") (pintype "power_in"))
      (node (ref "U43") (pin "67") (pinfunction "VIN_67") (pintype "power_in"))
    )
    (net (code "48") (name "unconnected-(U33-NC-Pad26)") (class "Default")
      (node (ref "U33") (pin "26") (pinfunction "NC_26") (pintype "passive+no_connect"))
    )
    (net (code "49") (name "unconnected-(U33-SPICK-Pad35)") (class "Default")
      (node (ref "U33") (pin "35") (pinfunction "SPICK_35") (pintype "passive+no_connect"))
    )
    (net (code "50") (name "unconnected-(U33-SPICS#-Pad34)") (class "Default")
      (node (ref "U33") (pin "34") (pinfunction "SPICS#_34") (pintype "passive+no_connect"))
    )
    (net (code "51") (name "unconnected-(U33-SPISI-Pad36)") (class "Default")
      (node (ref "U33") (pin "36") (pinfunction "SPISI_36") (pintype "passive+no_connect"))
    )
    (net (code "52") (name "unconnected-(U33-SPISO-Pad33)") (class "Default")
      (node (ref "U33") (pin "33") (pinfunction "SPISO_33") (pintype "passive+no_connect"))
    )
    (net (code "53") (name "unconnected-(U33-SSRX3+-Pad4)") (class "Default")
      (node (ref "U33") (pin "4") (pinfunction "SSRX3+_4") (pintype "passive+no_connect"))
    )
    (net (code "54") (name "unconnected-(U33-SSRX3--Pad5)") (class "Default")
      (node (ref "U33") (pin "5") (pinfunction "SSRX3-_5") (pintype "passive+no_connect"))
    )
    (net (code "55") (name "unconnected-(U33-SSRX4+-Pad13)") (class "Default")
      (node (ref "U33") (pin "13") (pinfunction "SSRX4+_13") (pintype "passive+no_connect"))
    )
    (net (code "56") (name "unconnected-(U33-SSRX4--Pad14)") (class "Default")
      (node (ref "U33") (pin "14") (pinfunction "SSRX4-_14") (pintype "passive+no_connect"))
    )
    (net (code "57") (name "unconnected-(U33-SSTX3+-Pad1)") (class "Default")
      (node (ref "U33") (pin "1") (pinfunction "SSTX3+_1") (pintype "passive+no_connect"))
    )
    (net (code "58") (name "unconnected-(U33-SSTX3--Pad2)") (class "Default")
      (node (ref "U33") (pin "2") (pinfunction "SSTX3-_2") (pintype "passive+no_connect"))
    )
    (net (code "59") (name "unconnected-(U33-SSTX4+-Pad10)") (class "Default")
      (node (ref "U33") (pin "10") (pinfunction "SSTX4+_10") (pintype "passive+no_connect"))
    )
    (net (code "60") (name "unconnected-(U33-SSTX4--Pad11)") (class "Default")
      (node (ref "U33") (pin "11") (pinfunction "SSTX4-_11") (pintype "passive+no_connect"))
    )
    (net (code "61") (name "unconnected-(U33-USB2D4+-Pad16)") (class "Default")
      (node (ref "U33") (pin "16") (pinfunction "USB2D4+_16") (pintype "passive+no_connect"))
    )
    (net (code "62") (name "unconnected-(U33-USB2D4--Pad17)") (class "Default")
      (node (ref "U33") (pin "17") (pinfunction "USB2D4-_17") (pintype "passive+no_connect"))
    )
    (net (code "63") (name "unconnected-(U33-USBHPE1#-Pad44)") (class "Default")
      (node (ref "U33") (pin "44") (pinfunction "USBHPE1#_44") (pintype "passive+no_connect"))
    )
    (net (code "64") (name "unconnected-(U33-USBHPE2#-Pad42)") (class "Default")
      (node (ref "U33") (pin "42") (pinfunction "USBHPE2#_42") (pintype "passive+no_connect"))
    )
    (net (code "65") (name "unconnected-(U33-USBHPE3#-Pad40)") (class "Default")
      (node (ref "U33") (pin "40") (pinfunction "USBHPE3#_40") (pintype "passive+no_connect"))
    )
    (net (code "66") (name "unconnected-(U33-USBHPE4#-Pad38)") (class "Default")
      (node (ref "U33") (pin "38") (pinfunction "USBHPE4#_38") (pintype "passive+no_connect"))
    )
    (net (code "67") (name "unconnected-(U43A-CLKREQ_L-Pad78)") (class "Default")
      (node (ref "U43") (pin "78") (pinfunction "CLKREQ_L_78") (pintype "power_in+no_connect"))
    )
    (net (code "68") (name "unconnected-(U43A-I2C_SCL-Pad50)") (class "Default")
      (node (ref "U43") (pin "50") (pinfunction "I2C_SCL_50") (pintype "passive+no_connect"))
    )
    (net (code "69") (name "unconnected-(U43A-I2C_SDA-Pad49)") (class "Default")
      (node (ref "U43") (pin "49") (pinfunction "I2C_SDA_49") (pintype "passive+no_connect"))
    )
    (net (code "70") (name "unconnected-(U43A-INTR-Pad77)") (class "Default")
      (node (ref "U43") (pin "77") (pinfunction "INTR_77") (pintype "power_in+no_connect"))
    )
    (net (code "71") (name "unconnected-(U43A-PHY_PRG-Pad84)") (class "Default")
      (node (ref "U43") (pin "84") (pinfunction "PHY_PRG_84") (pintype "power_in+no_connect"))
    )
    (net (code "72") (name "unconnected-(U43A-RESERVED-Pad52)") (class "Default")
      (node (ref "U43") (pin "52") (pinfunction "RESERVED_52") (pintype "passive+no_connect"))
    )
    (net (code "73") (name "unconnected-(U43A-RESERVED-Pad85)") (class "Default")
      (node (ref "U43") (pin "85") (pinfunction "RESERVED_85") (pintype "power_in+no_connect"))
    )
    (net (code "74") (name "unconnected-(U43A-SD_ALARM-Pad82)") (class "Default")
      (node (ref "U43") (pin "82") (pinfunction "SD_ALARM_82") (pintype "power_in+no_connect"))
    )
  )
)
